# SPI_FLASH.net
KiCad netlist of a schematic drawn in Altium Designer
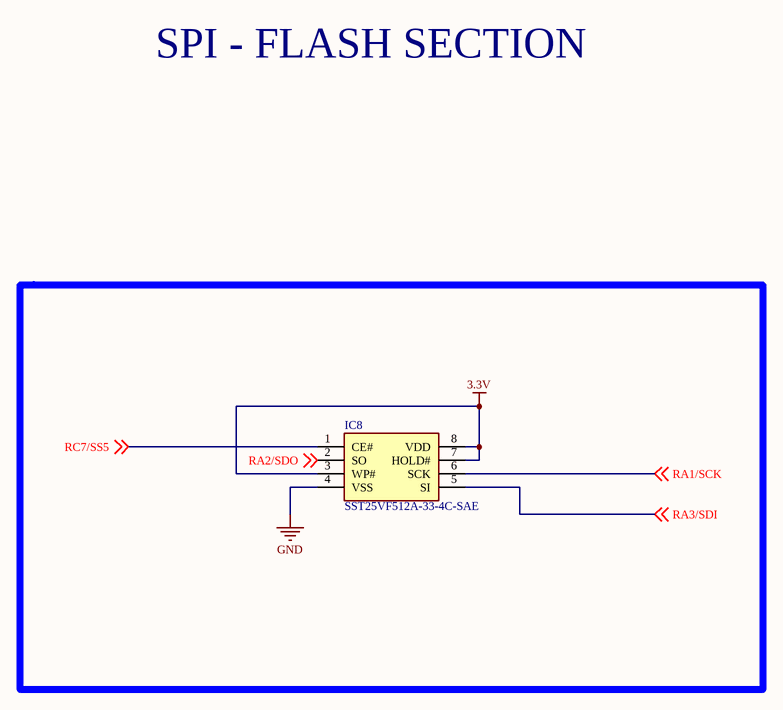
[diagram p0: SPI FLASH.SchDoc]

(export (version "E")
  (design (tool "Eeschema 10.0.6"))
  (components
    (comp (ref "IC8")
      (value "SST25VF512A-33-4C-SAE")
      (footprint "SamacSys:SOIC127P600X175-8N")
      (description "Integrated Circuit")
      (fields (field (name "MOUSER PART NUMBER") "804-25VF512A3CSAE"))
      (libsource (lib "*") (part "SST25VF512A-33-4C-SAE"))
    )
  )
  (nets
    (net (code "1") (name "3.3V") (class "Default")
      (node (ref "IC8") (pin "3") (pinfunction "WP#_3") (pintype "passive"))
      (node (ref "IC8") (pin "7") (pinfunction "HOLD#_7") (pintype "passive"))
      (node (ref "IC8") (pin "8") (pinfunction "VDD_8") (pintype "passive"))
    )
    (net (code "2") (name "GND") (class "Default")
      (node (ref "IC8") (pin "4") (pinfunction "VSS_4") (pintype "passive"))
    )
    (net (code "3") (name "RA1{slash}SCK") (class "Default")
      (node (ref "IC8") (pin "6") (pinfunction "SCK_6") (pintype "passive"))
    )
    (net (code "4") (name "RA2{slash}SDO") (class "Default")
      (node (ref "IC8") (pin "2") (pinfunction "SO_2") (pintype "passive"))
    )
    (net (code "5") (name "RA3{slash}SDI") (class "Default")
      (node (ref "IC8") (pin "5") (pinfunction "SI_5") (pintype "passive"))
    )
    (net (code "6") (name "RC7{slash}SS5") (class "Default")
      (node (ref "IC8") (pin "1") (pinfunction "CE#_1") (pintype "passive"))
    )
  )
)
